# PMIC_EA3036.net
KiCad netlist of a schematic drawn in Altium Designer
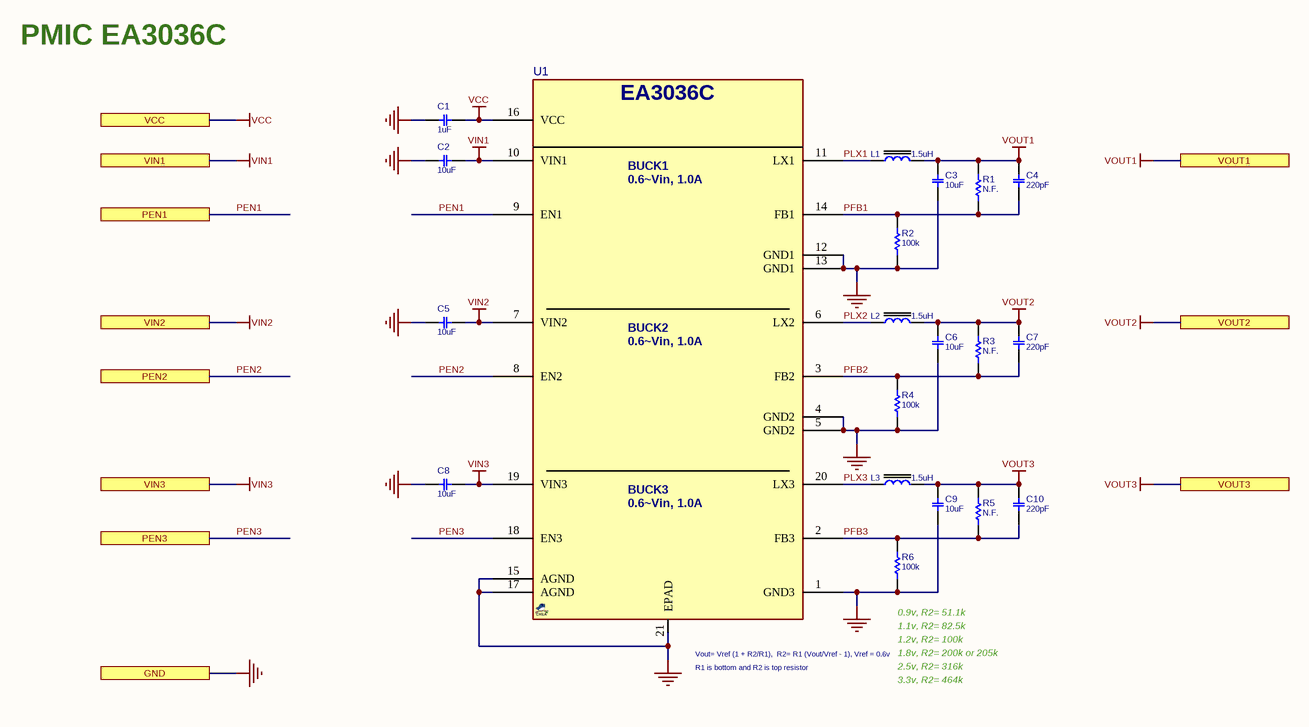
[diagram p0: PMIC_EA3036.SchDoc]

(export (version "E")
  (design (tool "Eeschema 10.0.6"))
  (components
    (comp (ref "C1")
      (value "1uF")
      (footprint "C0402")
      (description "CAP, MLCC")
      (fields (field (name "MANF_P#") "GMK105ABJ105KV-F") (field (name "MANF") "Taiyo Yuden"))
      (libsource (lib "passive_smd") (part "CAP_SMD_MLCC"))
    )
    (comp (ref "C2")
      (value "10uF")
      (footprint "C0402")
      (description "CAP, MLCC")
      (fields (field (name "MANF_P#") "CL05A106MP5NUNC") (field (name "MANF") "Samsung"))
      (libsource (lib "passive_smd") (part "CAP_SMD_MLCC"))
    )
    (comp (ref "C3")
      (value "10uF")
      (footprint "C0402")
      (description "CAP, MLCC")
      (fields (field (name "MANF_P#") "CL05A106MP5NUNC") (field (name "MANF") "Samsung"))
      (libsource (lib "passive_smd") (part "CAP_SMD_MLCC"))
    )
    (comp (ref "C4")
      (value "220pF")
      (footprint "C0402")
      (description "CAP, MLCC")
      (libsource (lib "passive_smd") (part "CAP_SMD_MLCC"))
    )
    (comp (ref "C5")
      (value "10uF")
      (footprint "C0402")
      (description "CAP, MLCC")
      (fields (field (name "MANF_P#") "CL05A106MP5NUNC") (field (name "MANF") "Samsung"))
      (libsource (lib "passive_smd") (part "CAP_SMD_MLCC"))
    )
    (comp (ref "C6")
      (value "10uF")
      (footprint "C0402")
      (description "CAP, MLCC")
      (fields (field (name "MANF_P#") "CL05A106MP5NUNC") (field (name "MANF") "Samsung"))
      (libsource (lib "passive_smd") (part "CAP_SMD_MLCC"))
    )
    (comp (ref "C7")
      (value "220pF")
      (footprint "C0402")
      (description "CAP, MLCC")
      (libsource (lib "passive_smd") (part "CAP_SMD_MLCC"))
    )
    (comp (ref "C8")
      (value "10uF")
      (footprint "C0402")
      (description "CAP, MLCC")
      (fields (field (name "MANF_P#") "CL05A106MP5NUNC") (field (name "MANF") "Samsung"))
      (libsource (lib "passive_smd") (part "CAP_SMD_MLCC"))
    )
    (comp (ref "C9")
      (value "10uF")
      (footprint "C0402")
      (description "CAP, MLCC")
      (fields (field (name "MANF_P#") "CL05A106MP5NUNC") (field (name "MANF") "Samsung"))
      (libsource (lib "passive_smd") (part "CAP_SMD_MLCC"))
    )
    (comp (ref "C10")
      (value "220pF")
      (footprint "C0402")
      (description "CAP, MLCC")
      (libsource (lib "passive_smd") (part "CAP_SMD_MLCC"))
    )
    (comp (ref "L1")
      (value "1.5uH")
      (footprint "L_3")
      (description "INDUCTOR")
      (fields (field (name "MANF_P#") "NRH3012T1R5NN"))
      (libsource (lib "inductor_power") (part "IND_SMD_2.2uH_2.6A"))
    )
    (comp (ref "L2")
      (value "1.5uH")
      (footprint "L_3")
      (description "INDUCTOR")
      (fields (field (name "MANF_P#") "NRH3012T1R5NN"))
      (libsource (lib "inductor_power") (part "IND_SMD_2.2uH_2.6A"))
    )
    (comp (ref "L3")
      (value "1.5uH")
      (footprint "L_3")
      (description "INDUCTOR")
      (fields (field (name "MANF_P#") "NRH3012T1R5NN"))
      (libsource (lib "inductor_power") (part "IND_SMD_2.2uH_2.6A"))
    )
    (comp (ref "R1")
      (value "N.F.")
      (footprint "R0402")
      (description "RESISTOR, SMD")
      (libsource (lib "passive_res_smd") (part "RES_SMD"))
    )
    (comp (ref "R2")
      (value "100k")
      (footprint "R0402")
      (description "RESISTOR, SMD")
      (libsource (lib "passive_res_smd") (part "RES_SMD"))
    )
    (comp (ref "R3")
      (value "N.F.")
      (footprint "R0402")
      (description "RESISTOR, SMD")
      (libsource (lib "passive_res_smd") (part "RES_SMD"))
    )
    (comp (ref "R4")
      (value "100k")
      (footprint "R0402")
      (description "RESISTOR, SMD")
      (libsource (lib "passive_res_smd") (part "RES_SMD"))
    )
    (comp (ref "R5")
      (value "N.F.")
      (footprint "R0402")
      (description "RESISTOR, SMD")
      (libsource (lib "passive_res_smd") (part "RES_SMD"))
    )
    (comp (ref "R6")
      (value "100k")
      (footprint "R0402")
      (description "RESISTOR, SMD")
      (libsource (lib "passive_res_smd") (part "RES_SMD"))
    )
    (comp (ref "U1")
      (value "EA3036C")
      (footprint "QFN40_20T")
      (description "IC, Regulator PMIC, 3DCDC 1.5MHz, total must be under 6W")
      (fields (field (name "MANF") "Everanalog") (field (name "MANF_P#") "EA3036CQBR"))
      (libsource (lib "pwr_reg_pmic") (part "EA3036C_QFN20"))
    )
  )
  (nets
    (net (code "1") (name "/PEN1") (class "Default")
      (node (ref "U1") (pin "9") (pinfunction "EN1_9") (pintype "passive"))
    )
    (net (code "2") (name "/PEN2") (class "Default")
      (node (ref "U1") (pin "8") (pinfunction "EN2_8") (pintype "passive"))
    )
    (net (code "3") (name "/PEN3") (class "Default")
      (node (ref "U1") (pin "18") (pinfunction "EN3_18") (pintype "passive"))
    )
    (net (code "4") (name "/PFB1") (class "Default")
      (node (ref "C4") (pin "1") (pinfunction "1_1") (pintype "passive"))
      (node (ref "R1") (pin "2") (pinfunction "2_2") (pintype "passive"))
      (node (ref "R2") (pin "1") (pinfunction "1_1") (pintype "passive"))
      (node (ref "U1") (pin "14") (pinfunction "FB1_14") (pintype "passive"))
    )
    (net (code "5") (name "/PFB2") (class "Default")
      (node (ref "C7") (pin "1") (pinfunction "1_1") (pintype "passive"))
      (node (ref "R3") (pin "2") (pinfunction "2_2") (pintype "passive"))
      (node (ref "R4") (pin "1") (pinfunction "1_1") (pintype "passive"))
      (node (ref "U1") (pin "3") (pinfunction "FB2_3") (pintype "passive"))
    )
    (net (code "6") (name "/PFB3") (class "Default")
      (node (ref "C10") (pin "1") (pinfunction "1_1") (pintype "passive"))
      (node (ref "R5") (pin "2") (pinfunction "2_2") (pintype "passive"))
      (node (ref "R6") (pin "1") (pinfunction "1_1") (pintype "passive"))
      (node (ref "U1") (pin "2") (pinfunction "FB3_2") (pintype "passive"))
    )
    (net (code "7") (name "/PLX1") (class "Default")
      (node (ref "L1") (pin "1") (pinfunction "1_1") (pintype "passive"))
      (node (ref "U1") (pin "11") (pinfunction "LX1_11") (pintype "passive"))
    )
    (net (code "8") (name "/PLX2") (class "Default")
      (node (ref "L2") (pin "1") (pinfunction "1_1") (pintype "passive"))
      (node (ref "U1") (pin "6") (pinfunction "LX2_6") (pintype "passive"))
    )
    (net (code "9") (name "/PLX3") (class "Default")
      (node (ref "L3") (pin "1") (pinfunction "1_1") (pintype "passive"))
      (node (ref "U1") (pin "20") (pinfunction "LX3_20") (pintype "passive"))
    )
    (net (code "10") (name "GND") (class "Default")
      (node (ref "C1") (pin "1") (pinfunction "1_1") (pintype "passive"))
      (node (ref "C2") (pin "1") (pinfunction "1_1") (pintype "passive"))
      (node (ref "C3") (pin "1") (pinfunction "1_1") (pintype "passive"))
      (node (ref "C5") (pin "1") (pinfunction "1_1") (pintype "passive"))
      (node (ref "C6") (pin "1") (pinfunction "1_1") (pintype "passive"))
      (node (ref "C8") (pin "1") (pinfunction "1_1") (pintype "passive"))
      (node (ref "C9") (pin "1") (pinfunction "1_1") (pintype "passive"))
      (node (ref "R2") (pin "2") (pinfunction "2_2") (pintype "passive"))
      (node (ref "R4") (pin "2") (pinfunction "2_2") (pintype "passive"))
      (node (ref "R6") (pin "2") (pinfunction "2_2") (pintype "passive"))
      (node (ref "U1") (pin "1") (pinfunction "GND3_1") (pintype "passive"))
      (node (ref "U1") (pin "12") (pinfunction "GND1_12") (pintype "passive"))
      (node (ref "U1") (pin "13") (pinfunction "GND1_13") (pintype "passive"))
      (node (ref "U1") (pin "15") (pinfunction "AGND_15") (pintype "passive"))
      (node (ref "U1") (pin "17") (pinfunction "AGND_17") (pintype "passive"))
      (node (ref "U1") (pin "21") (pinfunction "EPAD_21") (pintype "passive"))
      (node (ref "U1") (pin "4") (pinfunction "GND2_4") (pintype "passive"))
      (node (ref "U1") (pin "5") (pinfunction "GND2_5") (pintype "passive"))
    )
    (net (code "11") (name "VCC") (class "Default")
      (node (ref "C1") (pin "2") (pinfunction "2_2") (pintype "passive"))
      (node (ref "U1") (pin "16") (pinfunction "VCC_16") (pintype "passive"))
    )
    (net (code "12") (name "VIN1") (class "Default")
      (node (ref "C2") (pin "2") (pinfunction "2_2") (pintype "passive"))
      (node (ref "U1") (pin "10") (pinfunction "VIN1_10") (pintype "passive"))
    )
    (net (code "13") (name "VIN2") (class "Default")
      (node (ref "C5") (pin "2") (pinfunction "2_2") (pintype "passive"))
      (node (ref "U1") (pin "7") (pinfunction "VIN2_7") (pintype "passive"))
    )
    (net (code "14") (name "VIN3") (class "Default")
      (node (ref "C8") (pin "2") (pinfunction "2_2") (pintype "passive"))
      (node (ref "U1") (pin "19") (pinfunction "VIN3_19") (pintype "passive"))
    )
    (net (code "15") (name "VOUT1") (class "Default")
      (node (ref "C3") (pin "2") (pinfunction "2_2") (pintype "passive"))
      (node (ref "C4") (pin "2") (pinfunction "2_2") (pintype "passive"))
      (node (ref "L1") (pin "2") (pinfunction "2_2") (pintype "passive"))
      (node (ref "R1") (pin "1") (pinfunction "1_1") (pintype "passive"))
    )
    (net (code "16") (name "VOUT2") (class "Default")
      (node (ref "C6") (pin "2") (pinfunction "2_2") (pintype "passive"))
      (node (ref "C7") (pin "2") (pinfunction "2_2") (pintype "passive"))
      (node (ref "L2") (pin "2") (pinfunction "2_2") (pintype "passive"))
      (node (ref "R3") (pin "1") (pinfunction "1_1") (pintype "passive"))
    )
    (net (code "17") (name "VOUT3") (class "Default")
      (node (ref "C10") (pin "2") (pinfunction "2_2") (pintype "passive"))
      (node (ref "C9") (pin "2") (pinfunction "2_2") (pintype "passive"))
      (node (ref "L3") (pin "2") (pinfunction "2_2") (pintype "passive"))
      (node (ref "R5") (pin "1") (pinfunction "1_1") (pintype "passive"))
    )
  )
)
